# Current_Sense_Rev_2_2.net
KiCad netlist of a schematic drawn in EAGLE
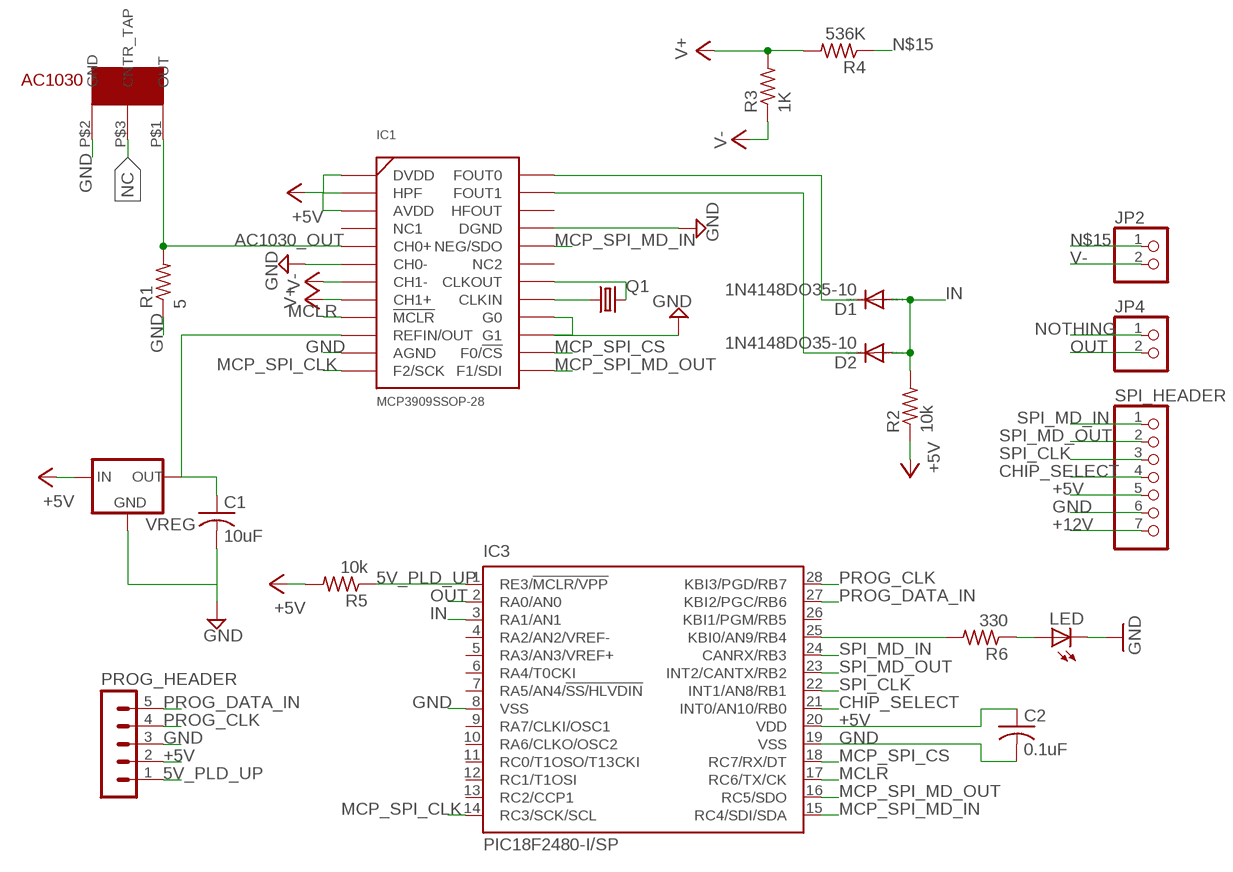
[diagram p0: schematic, sheet 1]

(export (version "E")
  (design (tool "Eeschema 10.0.6"))
  (components
    (comp (ref "AC1030")
      (value "AC1030")
      (footprint "eagle-import:AC1030")
      (libsource (lib "eagle-import") (part "AC1030"))
    )
    (comp (ref "C1")
      (value "10uF")
      (footprint "eagle-import:C025-024X044")
      (libsource (lib "eagle-import") (part "C-US025-024X044"))
    )
    (comp (ref "C2")
      (value "0.1uF")
      (footprint "eagle-import:C025-024X044")
      (libsource (lib "eagle-import") (part "C-US025-024X044"))
    )
    (comp (ref "D1")
      (value "1N4148DO35-10")
      (footprint "eagle-import:DO35-10")
      (libsource (lib "eagle-import") (part "1N4148DO35-10"))
    )
    (comp (ref "D2")
      (value "1N4148DO35-10")
      (footprint "eagle-import:DO35-10")
      (libsource (lib "eagle-import") (part "1N4148DO35-10"))
    )
    (comp (ref "IC1")
      (value "MCP3909SSOP-28")
      (footprint "eagle-import:SSOP-24")
      (libsource (lib "eagle-import") (part "MCP3909SSOP-28"))
    )
    (comp (ref "IC3")
      (value "PIC18F2480-I/SP")
      (footprint "eagle-import:DIL28-3")
      (fields (field (name "MF") "MICROCHIP"))
      (libsource (lib "eagle-import") (part "PIC18F280-I/SP4"))
    )
    (comp (ref "JP2")
      (value "PINHD-1X2")
      (footprint "eagle-import:1X02")
      (libsource (lib "eagle-import") (part "PINHD-1X2"))
    )
    (comp (ref "JP4")
      (value "PINHD-1X2")
      (footprint "eagle-import:1X02")
      (libsource (lib "eagle-import") (part "PINHD-1X2"))
    )
    (comp (ref "LED")
      (value "LED3MM")
      (footprint "eagle-import:LED3MM")
      (libsource (lib "eagle-import") (part "LED3MM"))
    )
    (comp (ref "PROG_HEADER")
      (value "MA05-1")
      (footprint "eagle-import:MA05-1")
      (libsource (lib "eagle-import") (part "MA05-1"))
    )
    (comp (ref "Q1")
      (value "CRYSTALHC49S")
      (footprint "eagle-import:HC49_S")
      (libsource (lib "eagle-import") (part "CRYSTALHC49S"))
    )
    (comp (ref "R1")
      (value "5")
      (footprint "eagle-import:0204_7")
      (libsource (lib "eagle-import") (part "R-US_0204/7"))
    )
    (comp (ref "R2")
      (value "10k")
      (footprint "eagle-import:0204_7")
      (libsource (lib "eagle-import") (part "R-US_0204/7"))
    )
    (comp (ref "R3")
      (value "1K")
      (footprint "eagle-import:0204_7")
      (libsource (lib "eagle-import") (part "R-US_0204/7"))
    )
    (comp (ref "R4")
      (value "536K")
      (footprint "eagle-import:0204_7")
      (libsource (lib "eagle-import") (part "R-US_0204/7"))
    )
    (comp (ref "R5")
      (value "10k")
      (footprint "eagle-import:0204_7")
      (libsource (lib "eagle-import") (part "R-US_0204/7"))
    )
    (comp (ref "R6")
      (value "330")
      (footprint "eagle-import:0204_7")
      (libsource (lib "eagle-import") (part "R-US_0204/7"))
    )
    (comp (ref "SPI_HEADER")
      (value "PINHD-1X7")
      (footprint "eagle-import:1X07")
      (libsource (lib "eagle-import") (part "PINHD-1X7"))
    )
    (comp (ref "VREG")
      (value "MCP1700INLINE")
      (footprint "eagle-import:TO92-INLINE")
      (libsource (lib "eagle-import") (part "MCP1700INLINE"))
    )
  )
  (nets
    (net (code "1") (name "+5V") (class "Default")
      (node (ref "C2") (pin "1") (pinfunction "1_1") (pintype "passive"))
      (node (ref "IC1") (pin "1") (pinfunction "DVDD_1") (pintype "bidirectional"))
      (node (ref "IC1") (pin "2") (pinfunction "HPF_2") (pintype "bidirectional"))
      (node (ref "IC1") (pin "3") (pinfunction "AVDD_3") (pintype "bidirectional"))
      (node (ref "IC3") (pin "20") (pinfunction "VDD_20") (pintype "power_in"))
      (node (ref "PROG_HEADER") (pin "2") (pinfunction "2_2") (pintype "passive"))
      (node (ref "R2") (pin "1") (pinfunction "1_1") (pintype "passive"))
      (node (ref "R5") (pin "2") (pinfunction "2_2") (pintype "passive"))
      (node (ref "SPI_HEADER") (pin "5") (pinfunction "5_5") (pintype "passive"))
      (node (ref "VREG") (pin "2") (pinfunction "IN_2") (pintype "input"))
    )
    (net (code "2") (name "/+12V") (class "Default")
      (node (ref "SPI_HEADER") (pin "7") (pinfunction "7_7") (pintype "passive"))
    )
    (net (code "3") (name "/5V_PLD_UP") (class "Default")
      (node (ref "IC3") (pin "1") (pinfunction "RE3/~{MCLR/VPP}_1") (pintype "input"))
      (node (ref "PROG_HEADER") (pin "1") (pinfunction "1_1") (pintype "passive"))
      (node (ref "R5") (pin "1") (pinfunction "1_1") (pintype "passive"))
    )
    (net (code "4") (name "/AC1030_OUT") (class "Default")
      (node (ref "AC1030") (pin "P$1") (pinfunction "OUT_P$1") (pintype "output"))
      (node (ref "IC1") (pin "5") (pinfunction "CH0+_5") (pintype "bidirectional"))
      (node (ref "R1") (pin "2") (pinfunction "2_2") (pintype "passive"))
    )
    (net (code "5") (name "/CHIP_SELECT") (class "Default")
      (node (ref "IC3") (pin "21") (pinfunction "INT0/AN10/RB0_21") (pintype "bidirectional"))
      (node (ref "SPI_HEADER") (pin "4") (pinfunction "4_4") (pintype "passive"))
    )
    (net (code "6") (name "/IN") (class "Default")
      (node (ref "D1") (pin "A") (pinfunction "A_A") (pintype "passive"))
      (node (ref "D2") (pin "A") (pinfunction "A_A") (pintype "passive"))
      (node (ref "IC3") (pin "3") (pinfunction "RA1/AN1_3") (pintype "bidirectional"))
      (node (ref "R2") (pin "2") (pinfunction "2_2") (pintype "passive"))
    )
    (net (code "7") (name "/MCLR") (class "Default")
      (node (ref "IC1") (pin "9") (pinfunction "~{MCLR}_9") (pintype "bidirectional"))
      (node (ref "IC3") (pin "17") (pinfunction "RC6/TX/CK_17") (pintype "bidirectional"))
    )
    (net (code "8") (name "/MCP_SPI_CLK") (class "Default")
      (node (ref "IC1") (pin "12") (pinfunction "F2/SCK_12") (pintype "bidirectional"))
      (node (ref "IC3") (pin "14") (pinfunction "RC3/SCK/SCL_14") (pintype "bidirectional"))
    )
    (net (code "9") (name "/MCP_SPI_CS") (class "Default")
      (node (ref "IC1") (pin "14") (pinfunction "F0/~{CS}_14") (pintype "bidirectional"))
      (node (ref "IC3") (pin "18") (pinfunction "RC7/RX/DT_18") (pintype "bidirectional"))
    )
    (net (code "10") (name "/MCP_SPI_MD_IN") (class "Default")
      (node (ref "IC1") (pin "20") (pinfunction "NEG/SDO_20") (pintype "bidirectional"))
      (node (ref "IC3") (pin "15") (pinfunction "RC4/SDI/SDA_15") (pintype "bidirectional"))
    )
    (net (code "11") (name "/MCP_SPI_MD_OUT") (class "Default")
      (node (ref "IC1") (pin "13") (pinfunction "F1/SDI_13") (pintype "bidirectional"))
      (node (ref "IC3") (pin "16") (pinfunction "RC5/SDO_16") (pintype "bidirectional"))
    )
    (net (code "12") (name "/N$15") (class "Default")
      (node (ref "JP2") (pin "1") (pinfunction "1_1") (pintype "passive"))
      (node (ref "R4") (pin "1") (pinfunction "1_1") (pintype "passive"))
    )
    (net (code "13") (name "/NOTHING") (class "Default")
      (node (ref "JP4") (pin "1") (pinfunction "1_1") (pintype "passive"))
    )
    (net (code "14") (name "/OUT") (class "Default")
      (node (ref "IC3") (pin "2") (pinfunction "RA0/AN0_2") (pintype "bidirectional"))
      (node (ref "JP4") (pin "2") (pinfunction "2_2") (pintype "passive"))
    )
    (net (code "15") (name "/PROG_CLK") (class "Default")
      (node (ref "IC3") (pin "28") (pinfunction "KBI3/PGD/RB7_28") (pintype "bidirectional"))
      (node (ref "PROG_HEADER") (pin "4") (pinfunction "4_4") (pintype "passive"))
    )
    (net (code "16") (name "/PROG_DATA_IN") (class "Default")
      (node (ref "IC3") (pin "27") (pinfunction "KBI2/PGC/RB6_27") (pintype "bidirectional"))
      (node (ref "PROG_HEADER") (pin "5") (pinfunction "5_5") (pintype "passive"))
    )
    (net (code "17") (name "/SPI_CLK") (class "Default")
      (node (ref "IC3") (pin "22") (pinfunction "INT1/AN8/RB1_22") (pintype "bidirectional"))
      (node (ref "SPI_HEADER") (pin "3") (pinfunction "3_3") (pintype "passive"))
    )
    (net (code "18") (name "/SPI_MD_IN") (class "Default")
      (node (ref "IC3") (pin "24") (pinfunction "CANRX/RB3_24") (pintype "bidirectional"))
      (node (ref "SPI_HEADER") (pin "1") (pinfunction "1_1") (pintype "passive"))
    )
    (net (code "19") (name "/SPI_MD_OUT") (class "Default")
      (node (ref "IC3") (pin "23") (pinfunction "INT2/CANTX/RB2_23") (pintype "bidirectional"))
      (node (ref "SPI_HEADER") (pin "2") (pinfunction "2_2") (pintype "passive"))
    )
    (net (code "20") (name "GND") (class "Default")
      (node (ref "AC1030") (pin "P$2") (pinfunction "GND_P$2") (pintype "output"))
      (node (ref "C1") (pin "2") (pinfunction "2_2") (pintype "passive"))
      (node (ref "C2") (pin "2") (pinfunction "2_2") (pintype "passive"))
      (node (ref "IC1") (pin "11") (pinfunction "AGND_11") (pintype "bidirectional"))
      (node (ref "IC1") (pin "15") (pinfunction "G1_15") (pintype "bidirectional"))
      (node (ref "IC1") (pin "16") (pinfunction "G0_16") (pintype "bidirectional"))
      (node (ref "IC1") (pin "21") (pinfunction "DGND_21") (pintype "bidirectional"))
      (node (ref "IC1") (pin "6") (pinfunction "CH0-_6") (pintype "bidirectional"))
      (node (ref "IC3") (pin "19") (pinfunction "VSS_19") (pintype "power_in"))
      (node (ref "IC3") (pin "8") (pinfunction "VSS_8") (pintype "power_in"))
      (node (ref "LED") (pin "K") (pinfunction "C_K") (pintype "passive"))
      (node (ref "PROG_HEADER") (pin "3") (pinfunction "3_3") (pintype "passive"))
      (node (ref "R1") (pin "1") (pinfunction "1_1") (pintype "passive"))
      (node (ref "SPI_HEADER") (pin "6") (pinfunction "6_6") (pintype "passive"))
      (node (ref "VREG") (pin "1") (pinfunction "GND_1") (pintype "input"))
    )
    (net (code "21") (name "NC") (class "Default")
      (node (ref "AC1030") (pin "P$3") (pinfunction "CNTR_TAP_P$3") (pintype "output"))
    )
    (net (code "22") (name "Net-(IC1-CLKIN)") (class "Default")
      (node (ref "IC1") (pin "17") (pinfunction "CLKIN_17") (pintype "bidirectional"))
      (node (ref "Q1") (pin "1") (pinfunction "1_1") (pintype "passive"))
    )
    (net (code "23") (name "Net-(IC1-CLKOUT)") (class "Default")
      (node (ref "IC1") (pin "18") (pinfunction "CLKOUT_18") (pintype "bidirectional"))
      (node (ref "Q1") (pin "2") (pinfunction "2_2") (pintype "passive"))
    )
    (net (code "24") (name "Net-(IC1-FOUT0)") (class "Default")
      (node (ref "D1") (pin "C") (pinfunction "C_C") (pintype "passive"))
      (node (ref "IC1") (pin "24") (pinfunction "FOUT0_24") (pintype "bidirectional"))
    )
    (net (code "25") (name "Net-(IC1-FOUT1)") (class "Default")
      (node (ref "D2") (pin "C") (pinfunction "C_C") (pintype "passive"))
      (node (ref "IC1") (pin "23") (pinfunction "FOUT1_23") (pintype "bidirectional"))
    )
    (net (code "26") (name "Net-(IC1-REFIN{slash}OUT)") (class "Default")
      (node (ref "C1") (pin "1") (pinfunction "1_1") (pintype "passive"))
      (node (ref "IC1") (pin "10") (pinfunction "REFIN/OUT_10") (pintype "bidirectional"))
      (node (ref "VREG") (pin "3") (pinfunction "OUT_3") (pintype "passive"))
    )
    (net (code "27") (name "Net-(IC3-KBI0{slash}AN9{slash}RB4)") (class "Default")
      (node (ref "IC3") (pin "25") (pinfunction "KBI0/AN9/RB4_25") (pintype "bidirectional"))
      (node (ref "R6") (pin "2") (pinfunction "2_2") (pintype "passive"))
    )
    (net (code "28") (name "Net-(LED-PadA)") (class "Default")
      (node (ref "LED") (pin "A") (pinfunction "A_A") (pintype "passive"))
      (node (ref "R6") (pin "1") (pinfunction "1_1") (pintype "passive"))
    )
    (net (code "29") (name "V+") (class "Default")
      (node (ref "IC1") (pin "8") (pinfunction "CH1+_8") (pintype "bidirectional"))
      (node (ref "R3") (pin "2") (pinfunction "2_2") (pintype "passive"))
      (node (ref "R4") (pin "2") (pinfunction "2_2") (pintype "passive"))
    )
    (net (code "30") (name "V-") (class "Default")
      (node (ref "IC1") (pin "7") (pinfunction "CH1-_7") (pintype "bidirectional"))
      (node (ref "JP2") (pin "2") (pinfunction "2_2") (pintype "passive"))
      (node (ref "R3") (pin "1") (pinfunction "1_1") (pintype "passive"))
    )
    (net (code "31") (name "unconnected-(IC1-HFOUT-Pad22)") (class "Default")
      (node (ref "IC1") (pin "22") (pinfunction "HFOUT_22") (pintype "bidirectional"))
    )
    (net (code "32") (name "unconnected-(IC1-NC1-Pad4)") (class "Default")
      (node (ref "IC1") (pin "4") (pinfunction "NC1_4") (pintype "bidirectional"))
    )
    (net (code "33") (name "unconnected-(IC1-NC2-Pad19)") (class "Default")
      (node (ref "IC1") (pin "19") (pinfunction "NC2_19") (pintype "bidirectional"))
    )
    (net (code "34") (name "unconnected-(IC3-KBI1{slash}PGM{slash}RB5-Pad26)") (class "Default")
      (node (ref "IC3") (pin "26") (pinfunction "KBI1/PGM/RB5_26") (pintype "bidirectional"))
    )
    (net (code "35") (name "unconnected-(IC3-RA2{slash}AN2{slash}VREF--Pad4)") (class "Default")
      (node (ref "IC3") (pin "4") (pinfunction "RA2/AN2/VREF-_4") (pintype "bidirectional"))
    )
    (net (code "36") (name "unconnected-(IC3-RA3{slash}AN3{slash}VREF+-Pad5)") (class "Default")
      (node (ref "IC3") (pin "5") (pinfunction "RA3/AN3/VREF+_5") (pintype "bidirectional"))
    )
    (net (code "37") (name "unconnected-(IC3-RA4{slash}T0CKI-Pad6)") (class "Default")
      (node (ref "IC3") (pin "6") (pinfunction "RA4/T0CKI_6") (pintype "bidirectional"))
    )
    (net (code "38") (name "unconnected-(IC3-RA5{slash}AN4{slash}~{SS{slash}HLVDIN}-Pad7)") (class "Default")
      (node (ref "IC3") (pin "7") (pinfunction "RA5/AN4/~{SS/HLVDIN}_7") (pintype "bidirectional"))
    )
    (net (code "39") (name "unconnected-(IC3-RA6{slash}CLKO{slash}OSC2-Pad10)") (class "Default")
      (node (ref "IC3") (pin "10") (pinfunction "RA6/CLKO/OSC2_10") (pintype "output"))
    )
    (net (code "40") (name "unconnected-(IC3-RA7{slash}CLKI{slash}OSC1-Pad9)") (class "Default")
      (node (ref "IC3") (pin "9") (pinfunction "RA7/CLKI/OSC1_9") (pintype "input"))
    )
    (net (code "41") (name "unconnected-(IC3-RC0{slash}T1OSO{slash}T13CKI-Pad11)") (class "Default")
      (node (ref "IC3") (pin "11") (pinfunction "RC0/T1OSO/T13CKI_11") (pintype "bidirectional"))
    )
    (net (code "42") (name "unconnected-(IC3-RC1{slash}T1OSI-Pad12)") (class "Default")
      (node (ref "IC3") (pin "12") (pinfunction "RC1/T1OSI_12") (pintype "bidirectional"))
    )
    (net (code "43") (name "unconnected-(IC3-RC2{slash}CCP1-Pad13)") (class "Default")
      (node (ref "IC3") (pin "13") (pinfunction "RC2/CCP1_13") (pintype "bidirectional"))
    )
  )
)
